# juan_foot.net
KiCad netlist of a schematic drawn in EAGLE
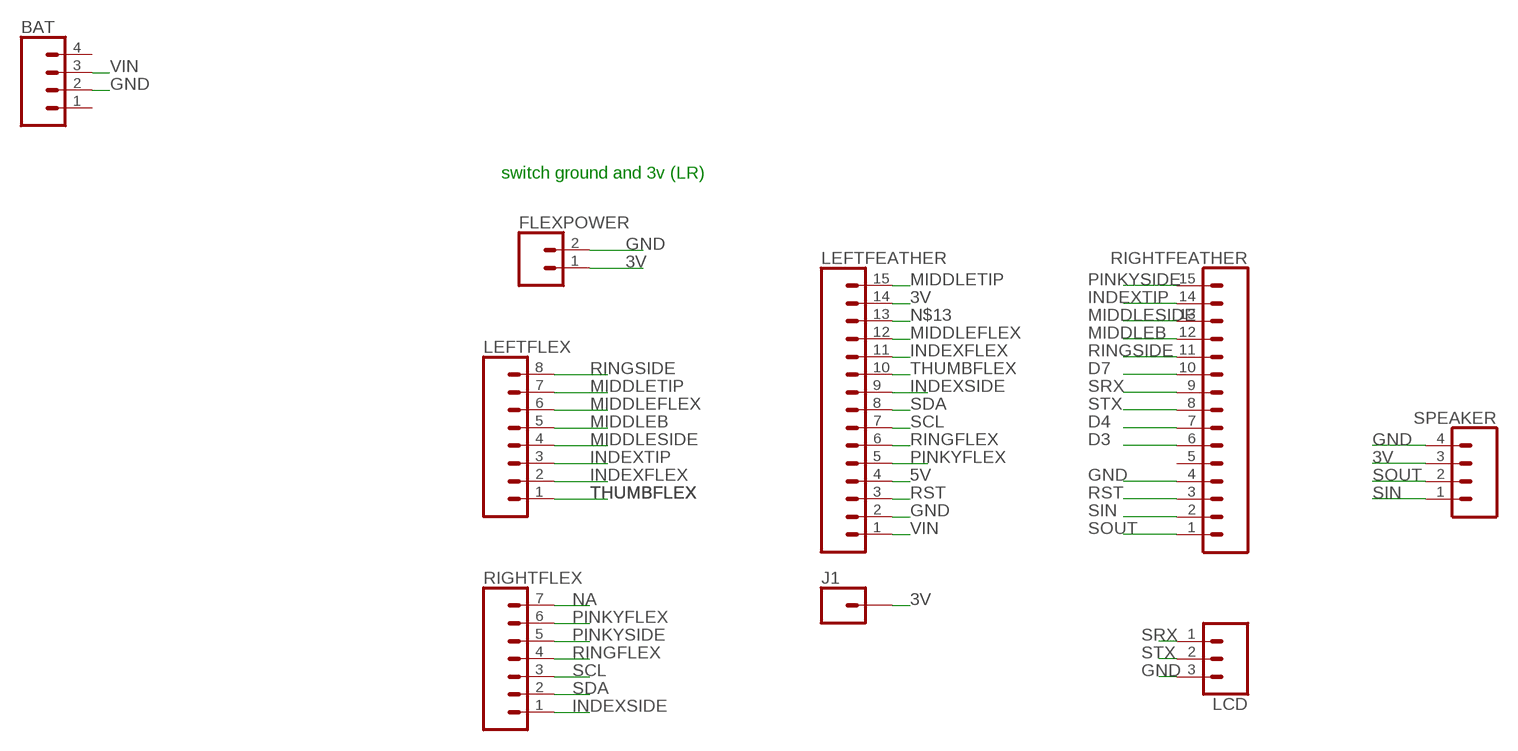
[diagram p0: schematic, sheet 1]

(export (version "E")
  (design (tool "Eeschema 10.0.6"))
  (components
    (comp (ref "BAT")
      (value "CONN_04")
      (footprint "eagle-import:1X04")
      (libsource (lib "eagle-import") (part "CONN_04"))
    )
    (comp (ref "FLEXPOWER")
      (value "CONN_02")
      (footprint "eagle-import:1X02")
      (libsource (lib "eagle-import") (part "CONN_02"))
    )
    (comp (ref "J1")
      (value "CONN_01")
      (footprint "eagle-import:1X01")
      (libsource (lib "eagle-import") (part "CONN_01"))
    )
    (comp (ref "LCD")
      (value "CONN_03")
      (footprint "eagle-import:1X03")
      (libsource (lib "eagle-import") (part "CONN_03"))
    )
    (comp (ref "LEFTFEATHER")
      (value "CONN_15")
      (footprint "eagle-import:1X15")
      (libsource (lib "eagle-import") (part "CONN_15"))
    )
    (comp (ref "LEFTFLEX")
      (value "CONN_08\"")
      (footprint "eagle-import:1X08")
      (libsource (lib "eagle-import") (part "CONN_08{dblquote}"))
    )
    (comp (ref "RIGHTFEATHER")
      (value "CONN_15")
      (footprint "eagle-import:1X15")
      (libsource (lib "eagle-import") (part "CONN_15"))
    )
    (comp (ref "RIGHTFLEX")
      (value "CONN_07")
      (footprint "eagle-import:1X07")
      (libsource (lib "eagle-import") (part "CONN_07"))
    )
    (comp (ref "SPEAKER")
      (value "CONN_04")
      (footprint "eagle-import:1X04")
      (libsource (lib "eagle-import") (part "CONN_04"))
    )
  )
  (nets
    (net (code "1") (name "/3V") (class "Default")
      (node (ref "FLEXPOWER") (pin "1") (pinfunction "1_1") (pintype "passive"))
      (node (ref "J1") (pin "1") (pinfunction "1_1") (pintype "passive"))
      (node (ref "LEFTFEATHER") (pin "14") (pinfunction "14_14") (pintype "passive"))
      (node (ref "SPEAKER") (pin "3") (pinfunction "3_3") (pintype "passive"))
    )
    (net (code "2") (name "/5V") (class "Default")
      (node (ref "LEFTFEATHER") (pin "4") (pinfunction "4_4") (pintype "passive"))
    )
    (net (code "3") (name "/D3") (class "Default")
      (node (ref "RIGHTFEATHER") (pin "6") (pinfunction "6_6") (pintype "passive"))
    )
    (net (code "4") (name "/D4") (class "Default")
      (node (ref "RIGHTFEATHER") (pin "7") (pinfunction "7_7") (pintype "passive"))
    )
    (net (code "5") (name "/D7") (class "Default")
      (node (ref "RIGHTFEATHER") (pin "10") (pinfunction "10_10") (pintype "passive"))
    )
    (net (code "6") (name "/GND") (class "Default")
      (node (ref "BAT") (pin "2") (pinfunction "2_2") (pintype "passive"))
      (node (ref "FLEXPOWER") (pin "2") (pinfunction "2_2") (pintype "passive"))
      (node (ref "LCD") (pin "3") (pinfunction "3_3") (pintype "passive"))
      (node (ref "LEFTFEATHER") (pin "2") (pinfunction "2_2") (pintype "passive"))
      (node (ref "RIGHTFEATHER") (pin "4") (pinfunction "4_4") (pintype "passive"))
      (node (ref "SPEAKER") (pin "4") (pinfunction "4_4") (pintype "passive"))
    )
    (net (code "7") (name "/INDEXFLEX") (class "Default")
      (node (ref "LEFTFEATHER") (pin "11") (pinfunction "11_11") (pintype "passive"))
      (node (ref "LEFTFLEX") (pin "2") (pinfunction "2_2") (pintype "passive"))
    )
    (net (code "8") (name "/INDEXSIDE") (class "Default")
      (node (ref "LEFTFEATHER") (pin "9") (pinfunction "9_9") (pintype "passive"))
      (node (ref "RIGHTFLEX") (pin "1") (pinfunction "1_1") (pintype "passive"))
    )
    (net (code "9") (name "/INDEXTIP") (class "Default")
      (node (ref "LEFTFLEX") (pin "3") (pinfunction "3_3") (pintype "passive"))
      (node (ref "RIGHTFEATHER") (pin "14") (pinfunction "14_14") (pintype "passive"))
    )
    (net (code "10") (name "/MIDDLEB") (class "Default")
      (node (ref "LEFTFLEX") (pin "5") (pinfunction "5_5") (pintype "passive"))
      (node (ref "RIGHTFEATHER") (pin "12") (pinfunction "12_12") (pintype "passive"))
    )
    (net (code "11") (name "/MIDDLEFLEX") (class "Default")
      (node (ref "LEFTFEATHER") (pin "12") (pinfunction "12_12") (pintype "passive"))
      (node (ref "LEFTFLEX") (pin "6") (pinfunction "6_6") (pintype "passive"))
    )
    (net (code "12") (name "/MIDDLESIDE") (class "Default")
      (node (ref "LEFTFLEX") (pin "4") (pinfunction "4_4") (pintype "passive"))
      (node (ref "RIGHTFEATHER") (pin "13") (pinfunction "13_13") (pintype "passive"))
    )
    (net (code "13") (name "/MIDDLETIP") (class "Default")
      (node (ref "LEFTFEATHER") (pin "15") (pinfunction "15_15") (pintype "passive"))
      (node (ref "LEFTFLEX") (pin "7") (pinfunction "7_7") (pintype "passive"))
    )
    (net (code "14") (name "/N$13") (class "Default")
      (node (ref "LEFTFEATHER") (pin "13") (pinfunction "13_13") (pintype "passive"))
    )
    (net (code "15") (name "/NA") (class "Default")
      (node (ref "RIGHTFLEX") (pin "7") (pinfunction "7_7") (pintype "passive"))
    )
    (net (code "16") (name "/PINKYFLEX") (class "Default")
      (node (ref "LEFTFEATHER") (pin "5") (pinfunction "5_5") (pintype "passive"))
      (node (ref "RIGHTFLEX") (pin "6") (pinfunction "6_6") (pintype "passive"))
    )
    (net (code "17") (name "/PINKYSIDE") (class "Default")
      (node (ref "RIGHTFEATHER") (pin "15") (pinfunction "15_15") (pintype "passive"))
      (node (ref "RIGHTFLEX") (pin "5") (pinfunction "5_5") (pintype "passive"))
    )
    (net (code "18") (name "/RINGFLEX") (class "Default")
      (node (ref "LEFTFEATHER") (pin "6") (pinfunction "6_6") (pintype "passive"))
      (node (ref "RIGHTFLEX") (pin "4") (pinfunction "4_4") (pintype "passive"))
    )
    (net (code "19") (name "/RINGSIDE") (class "Default")
      (node (ref "LEFTFLEX") (pin "8") (pinfunction "8_8") (pintype "passive"))
      (node (ref "RIGHTFEATHER") (pin "11") (pinfunction "11_11") (pintype "passive"))
    )
    (net (code "20") (name "/RST") (class "Default")
      (node (ref "LEFTFEATHER") (pin "3") (pinfunction "3_3") (pintype "passive"))
      (node (ref "RIGHTFEATHER") (pin "3") (pinfunction "3_3") (pintype "passive"))
    )
    (net (code "21") (name "/SCL") (class "Default")
      (node (ref "LEFTFEATHER") (pin "7") (pinfunction "7_7") (pintype "passive"))
      (node (ref "RIGHTFLEX") (pin "3") (pinfunction "3_3") (pintype "passive"))
    )
    (net (code "22") (name "/SDA") (class "Default")
      (node (ref "LEFTFEATHER") (pin "8") (pinfunction "8_8") (pintype "passive"))
      (node (ref "RIGHTFLEX") (pin "2") (pinfunction "2_2") (pintype "passive"))
    )
    (net (code "23") (name "/SIN") (class "Default")
      (node (ref "RIGHTFEATHER") (pin "2") (pinfunction "2_2") (pintype "passive"))
      (node (ref "SPEAKER") (pin "1") (pinfunction "1_1") (pintype "passive"))
    )
    (net (code "24") (name "/SOUT") (class "Default")
      (node (ref "RIGHTFEATHER") (pin "1") (pinfunction "1_1") (pintype "passive"))
      (node (ref "SPEAKER") (pin "2") (pinfunction "2_2") (pintype "passive"))
    )
    (net (code "25") (name "/SRX") (class "Default")
      (node (ref "LCD") (pin "1") (pinfunction "1_1") (pintype "passive"))
      (node (ref "RIGHTFEATHER") (pin "9") (pinfunction "9_9") (pintype "passive"))
    )
    (net (code "26") (name "/STX") (class "Default")
      (node (ref "LCD") (pin "2") (pinfunction "2_2") (pintype "passive"))
      (node (ref "RIGHTFEATHER") (pin "8") (pinfunction "8_8") (pintype "passive"))
    )
    (net (code "27") (name "/THUMBFLEX") (class "Default")
      (node (ref "LEFTFEATHER") (pin "10") (pinfunction "10_10") (pintype "passive"))
      (node (ref "LEFTFLEX") (pin "1") (pinfunction "1_1") (pintype "passive"))
    )
    (net (code "28") (name "/VIN") (class "Default")
      (node (ref "BAT") (pin "3") (pinfunction "3_3") (pintype "passive"))
      (node (ref "LEFTFEATHER") (pin "1") (pinfunction "1_1") (pintype "passive"))
    )
    (net (code "29") (name "unconnected-(BAT-Pad1)") (class "Default")
      (node (ref "BAT") (pin "1") (pinfunction "1_1") (pintype "passive"))
    )
    (net (code "30") (name "unconnected-(BAT-Pad4)") (class "Default")
      (node (ref "BAT") (pin "4") (pinfunction "4_4") (pintype "passive"))
    )
    (net (code "31") (name "unconnected-(RIGHTFEATHER-Pad5)") (class "Default")
      (node (ref "RIGHTFEATHER") (pin "5") (pinfunction "5_5") (pintype "passive"))
    )
  )
)
